# ExampleSchematic2.net
KiCad netlist of a schematic drawn in Altium Designer
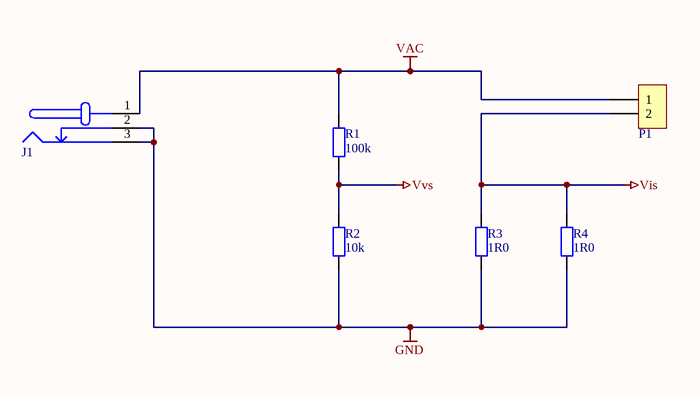
[diagram p0: ExampleSchematic2.SchDoc]

(export (version "E")
  (design (tool "Eeschema 10.0.6"))
  (components
    (comp (ref "J1")
      (value "DC barrel jack")
      (footprint "AC-Socket")
      (description "DC barrel jack connection to AC source")
      (libsource (lib "EE209_Library") (part "AC_Input"))
    )
    (comp (ref "P1")
      (value "Dual Banana Plugs")
      (footprint "Dual Banana Plug")
      (description "Dual banana plugs connection to the AC load")
      (fields (field (name "PUBLISHER") "Altium Limited"))
      (libsource (lib "EE209_Library") (part "AC_Output"))
    )
    (comp (ref "R1")
      (value "100k")
      (footprint "AXIAL-0.4")
      (description "Through hole resistor")
      (fields (field (name "PUBLISHER") "Altium Limited"))
      (libsource (lib "EE209_Library") (part "Res_TH_0AX4"))
    )
    (comp (ref "R2")
      (value "10k")
      (footprint "AXIAL-0.4")
      (description "Through hole resistor")
      (fields (field (name "PUBLISHER") "Altium Limited"))
      (libsource (lib "EE209_Library") (part "Res_TH_0AX4"))
    )
    (comp (ref "R3")
      (value "1R0")
      (footprint "AXIAL-0.4")
      (description "Through hole resistor")
      (fields (field (name "PUBLISHER") "Altium Limited"))
      (libsource (lib "EE209_Library") (part "Res_TH_0AX4"))
    )
    (comp (ref "R4")
      (value "1R0")
      (footprint "AXIAL-0.4")
      (description "Through hole resistor")
      (fields (field (name "PUBLISHER") "Altium Limited"))
      (libsource (lib "EE209_Library") (part "Res_TH_0AX4"))
    )
  )
  (nets
    (net (code "1") (name "GND") (class "Default")
      (node (ref "J1") (pin "2") (pinfunction "GND_ALT_2") (pintype "power_in"))
      (node (ref "J1") (pin "3") (pinfunction "GND_3") (pintype "power_in"))
      (node (ref "R2") (pin "1") (pinfunction "1_1") (pintype "passive"))
      (node (ref "R3") (pin "1") (pinfunction "1_1") (pintype "passive"))
      (node (ref "R4") (pin "1") (pinfunction "1_1") (pintype "passive"))
    )
    (net (code "2") (name "VAC") (class "Default")
      (node (ref "J1") (pin "1") (pinfunction "VCC_1") (pintype "power_in"))
      (node (ref "P1") (pin "1") (pinfunction "1_1") (pintype "passive"))
      (node (ref "R1") (pin "2") (pinfunction "2_2") (pintype "passive"))
    )
    (net (code "3") (name "Vis") (class "Default")
      (node (ref "P1") (pin "2") (pinfunction "2_2") (pintype "passive"))
      (node (ref "R3") (pin "2") (pinfunction "2_2") (pintype "passive"))
      (node (ref "R4") (pin "2") (pinfunction "2_2") (pintype "passive"))
    )
    (net (code "4") (name "Vvs") (class "Default")
      (node (ref "R1") (pin "1") (pinfunction "1_1") (pintype "passive"))
      (node (ref "R2") (pin "2") (pinfunction "2_2") (pintype "passive"))
    )
  )
)
